# fuenteProgramable.net
KiCad netlist of a schematic drawn in Altium Designer
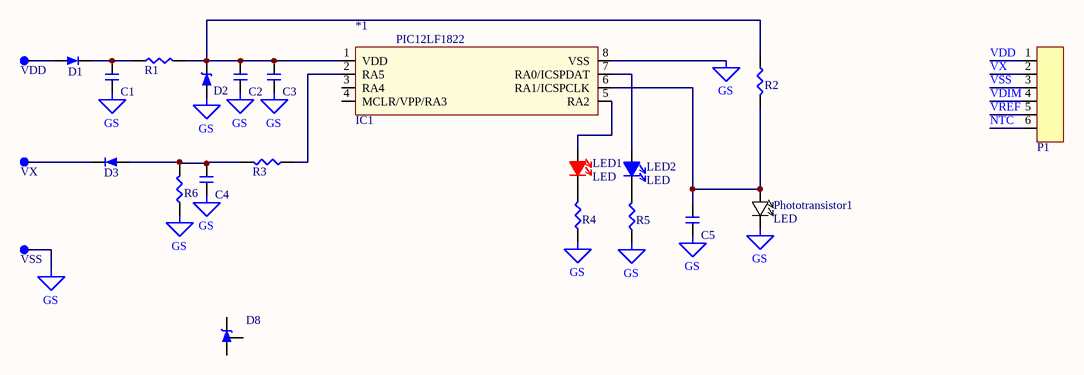
[diagram p0: fuenteProgramable.SchDoc]

(export (version "E")
  (design (tool "Eeschema 10.0.6"))
  (components
    (comp (ref "*1") (value "IC1") (footprint "SOIC-8") (libsource (lib "PIC12F1822") (part "Component_1")))
    (comp (ref "C1")
      (value "Capacitor")
      (footprint "0805")
      (libsource (lib "Italavia_001") (part "Capacitor"))
    )
    (comp (ref "C2")
      (value "Capacitor")
      (footprint "0805")
      (libsource (lib "Italavia_001") (part "Capacitor"))
    )
    (comp (ref "C3")
      (value "Capacitor")
      (footprint "0805")
      (libsource (lib "Italavia_001") (part "Capacitor"))
    )
    (comp (ref "C4")
      (value "Capacitor")
      (footprint "0805")
      (libsource (lib "Italavia_001") (part "Capacitor"))
    )
    (comp (ref "C5")
      (value "Capacitor")
      (footprint "0805")
      (libsource (lib "Italavia_001") (part "Capacitor"))
    )
    (comp (ref "D1") (value "Diodo") (footprint "0805") (libsource (lib "Italavia_001") (part "Diodo")))
    (comp (ref "D2") (value "Zener") (footprint "MINIMELF") (libsource (lib "Zener") (part "Zener")))
    (comp (ref "D3") (value "Diodo") (footprint "0805") (libsource (lib "Italavia_001") (part "Diodo")))
    (comp (ref "D8") (value "TL431") (footprint "SOT23") (libsource (lib "Componentes") (part "TL431")))
    (comp (ref "LED1")
      (value "LED")
      (footprint "LED Red 3mm TH V")
      (description "LED Red")
      (libsource (lib "IFS_Altium") (part "LED Red"))
    )
    (comp (ref "LED2")
      (value "LED")
      (footprint "LED Blue 3mm TH V")
      (description "LED Blue")
      (libsource (lib "IFS_Altium") (part "LED Blue"))
    )
    (comp (ref "P1")
      (value "C6pin")
      (footprint "C6PB")
      (description "Conector 6 pines")
      (libsource (lib "Conectores") (part "C6pin"))
    )
    (comp (ref "Phototransistor1")
      (value "LED")
      (footprint "LED White 3mm TH V")
      (description "LED White")
      (libsource (lib "IFS_Altium") (part "LED White"))
    )
    (comp (ref "R1")
      (value "Resistencia")
      (footprint "0805")
      (libsource (lib "Italavia_001") (part "Resistencia"))
    )
    (comp (ref "R2")
      (value "Resistencia")
      (footprint "0805")
      (libsource (lib "Italavia_001") (part "Resistencia"))
    )
    (comp (ref "R3")
      (value "Resistencia")
      (footprint "0805")
      (libsource (lib "Italavia_001") (part "Resistencia"))
    )
    (comp (ref "R4")
      (value "Resistencia")
      (footprint "0805")
      (libsource (lib "Italavia_001") (part "Resistencia"))
    )
    (comp (ref "R5")
      (value "Resistencia")
      (footprint "0805")
      (libsource (lib "Italavia_001") (part "Resistencia"))
    )
    (comp (ref "R6")
      (value "Resistencia")
      (footprint "0805")
      (libsource (lib "Italavia_001") (part "Resistencia"))
    )
    (comp (ref "VDD") (value "Pad") (footprint "Pad3x5") (libsource (lib "Italavia_001") (part "Pad")))
    (comp (ref "VSS") (value "Pad") (footprint "Pad3x5") (libsource (lib "Italavia_001") (part "Pad")))
    (comp (ref "VX") (value "Pad") (footprint "Pad3x5") (libsource (lib "Italavia_001") (part "Pad")))
  )
  (nets
    (net (code "1") (name "/NTC") (class "Default")
      (node (ref "P1") (pin "6") (pinfunction "6_6") (pintype "passive"))
    )
    (net (code "2") (name "/VDD") (class "Default")
      (node (ref "P1") (pin "1") (pinfunction "1_1") (pintype "passive"))
    )
    (net (code "3") (name "/VDIM") (class "Default")
      (node (ref "P1") (pin "4") (pinfunction "4_4") (pintype "passive"))
    )
    (net (code "4") (name "/VREF") (class "Default")
      (node (ref "P1") (pin "5") (pinfunction "5_5") (pintype "passive"))
    )
    (net (code "5") (name "/VSS") (class "Default")
      (node (ref "P1") (pin "3") (pinfunction "3_3") (pintype "passive"))
    )
    (net (code "6") (name "/VX") (class "Default")
      (node (ref "P1") (pin "2") (pinfunction "2_2") (pintype "passive"))
    )
    (net (code "7") (name "GS") (class "Default")
      (node (ref "*1") (pin "8") (pinfunction "VSS_8") (pintype "passive"))
      (node (ref "C1") (pin "1") (pintype "passive"))
      (node (ref "C2") (pin "2") (pintype "passive"))
      (node (ref "C3") (pin "2") (pintype "passive"))
      (node (ref "C4") (pin "2") (pintype "passive"))
      (node (ref "C5") (pin "2") (pintype "passive"))
      (node (ref "D2") (pin "2") (pintype "passive"))
      (node (ref "Phototransistor1") (pin "1") (pinfunction "1_1") (pintype "passive"))
      (node (ref "R4") (pin "1") (pintype "passive"))
      (node (ref "R5") (pin "1") (pintype "passive"))
      (node (ref "R6") (pin "1") (pintype "passive"))
      (node (ref "VSS") (pin "0") (pinfunction "0_0") (pintype "passive"))
    )
    (net (code "8") (name "Net-(*1-RA0{slash}ICSPDAT)") (class "Default")
      (node (ref "*1") (pin "7") (pinfunction "RA0/ICSPDAT_7") (pintype "passive"))
      (node (ref "LED2") (pin "2") (pinfunction "2_2") (pintype "passive"))
    )
    (net (code "9") (name "Net-(*1-RA1{slash}ICSPCLK)") (class "Default")
      (node (ref "*1") (pin "6") (pinfunction "RA1/ICSPCLK_6") (pintype "passive"))
      (node (ref "C5") (pin "1") (pintype "passive"))
      (node (ref "Phototransistor1") (pin "2") (pinfunction "2_2") (pintype "passive"))
      (node (ref "R2") (pin "2") (pinfunction "2_2") (pintype "passive"))
    )
    (net (code "10") (name "Net-(*1-RA2)") (class "Default")
      (node (ref "*1") (pin "5") (pinfunction "RA2_5") (pintype "passive"))
      (node (ref "LED1") (pin "2") (pinfunction "2_2") (pintype "passive"))
    )
    (net (code "11") (name "Net-(*1-RA5)") (class "Default")
      (node (ref "*1") (pin "2") (pinfunction "RA5_2") (pintype "passive"))
      (node (ref "R3") (pin "1") (pintype "passive"))
    )
    (net (code "12") (name "Net-(*1-VDD)") (class "Default")
      (node (ref "*1") (pin "1") (pinfunction "VDD_1") (pintype "passive"))
      (node (ref "C2") (pin "1") (pintype "passive"))
      (node (ref "C3") (pin "1") (pintype "passive"))
      (node (ref "D2") (pin "1") (pintype "passive"))
      (node (ref "R1") (pin "2") (pinfunction "2_2") (pintype "passive"))
      (node (ref "R2") (pin "1") (pintype "passive"))
    )
    (net (code "13") (name "Net-(C1-Pad2)") (class "Default")
      (node (ref "C1") (pin "2") (pintype "passive"))
      (node (ref "D1") (pin "1") (pintype "passive"))
      (node (ref "R1") (pin "1") (pintype "passive"))
    )
    (net (code "14") (name "Net-(C4-Pad1)") (class "Default")
      (node (ref "C4") (pin "1") (pintype "passive"))
      (node (ref "D3") (pin "2") (pintype "passive"))
      (node (ref "R3") (pin "2") (pinfunction "2_2") (pintype "passive"))
      (node (ref "R6") (pin "2") (pinfunction "2_2") (pintype "passive"))
    )
    (net (code "15") (name "Net-(D1-Pad2)") (class "Default")
      (node (ref "D1") (pin "2") (pintype "passive"))
      (node (ref "VDD") (pin "0") (pinfunction "0_0") (pintype "passive"))
    )
    (net (code "16") (name "Net-(D3-Pad1)") (class "Default")
      (node (ref "D3") (pin "1") (pintype "passive"))
      (node (ref "VX") (pin "0") (pinfunction "0_0") (pintype "passive"))
    )
    (net (code "17") (name "Net-(LED1-Pad1)") (class "Default")
      (node (ref "LED1") (pin "1") (pinfunction "1_1") (pintype "passive"))
      (node (ref "R4") (pin "2") (pinfunction "2_2") (pintype "passive"))
    )
    (net (code "18") (name "Net-(LED2-Pad1)") (class "Default")
      (node (ref "LED2") (pin "1") (pinfunction "1_1") (pintype "passive"))
      (node (ref "R5") (pin "2") (pinfunction "2_2") (pintype "passive"))
    )
    (net (code "19") (name "unconnected-(*1-MCLR{slash}VPP{slash}RA3-Pad4)") (class "Default")
      (node (ref "*1") (pin "4") (pinfunction "MCLR/VPP/RA3_4") (pintype "passive"))
    )
    (net (code "20") (name "unconnected-(*1-RA4-Pad3)") (class "Default")
      (node (ref "*1") (pin "3") (pinfunction "RA4_3") (pintype "passive"))
    )
    (net (code "21") (name "unconnected-(D8-Pad1)") (class "Default")
      (node (ref "D8") (pin "1") (pintype "passive"))
    )
    (net (code "22") (name "unconnected-(D8-Pad2)") (class "Default")
      (node (ref "D8") (pin "2") (pintype "passive"))
    )
    (net (code "23") (name "unconnected-(D8-Pad3)") (class "Default")
      (node (ref "D8") (pin "3") (pintype "passive"))
    )
  )
)
